# 02_-_MCU.net
KiCad netlist of a schematic drawn in Altium Designer
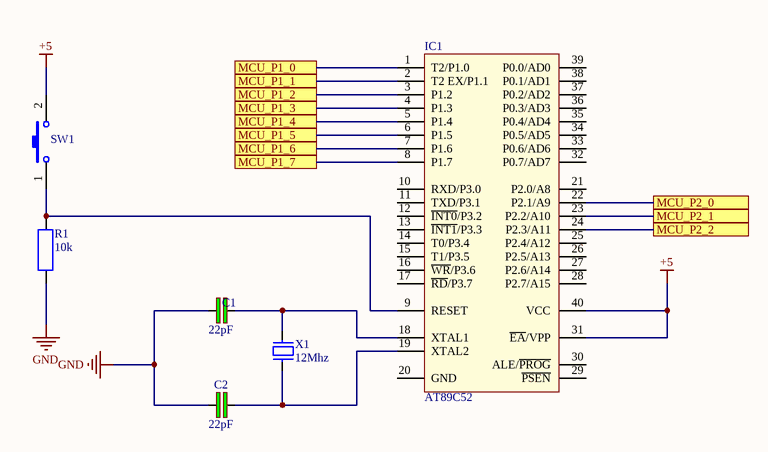
[diagram p0: [02] - MCU.SchDoc]

(export (version "E")
  (design (tool "Eeschema 10.0.6"))
  (components
    (comp (ref "C1")
      (value "22pF")
      (footprint "CAP_0805")
      (description "Cap SMD")
      (libsource (lib "My Library") (part "C"))
    )
    (comp (ref "C2")
      (value "22pF")
      (footprint "CAP_0805")
      (description "Cap SMD")
      (libsource (lib "My Library") (part "C"))
    )
    (comp (ref "IC1")
      (value "AT89C52")
      (footprint "DIP40/W0.6")
      (description "Atmel AT89C52, 8k Byte Flash Memory , 40 Pin")
      (libsource (lib "My Library") (part "AT89C52"))
    )
    (comp (ref "R1")
      (value "10k")
      (footprint "RES_SMD_0805")
      (description "Resistor 1W")
      (libsource (lib "My Library") (part "R1W"))
    )
    (comp (ref "SW1")
      (value "SW-2P-S")
      (footprint "SW-2P-S")
      (description "Switch Small 2 Pin")
      (fields (field (name "PUBLISHER") "Altium Limited"))
      (libsource (lib "My Library") (part "SW-2PIN-SMALL"))
    )
    (comp (ref "X1")
      (value "12Mhz")
      (footprint "XT2")
      (description "Crystal For all Crystal 2pin.")
      (libsource (lib "My Library") (part "XT2"))
    )
  )
  (nets
    (net (code "1") (name "+5") (class "Default")
      (node (ref "IC1") (pin "31") (pinfunction "~{EA}/VPP_31") (pintype "passive"))
      (node (ref "IC1") (pin "40") (pinfunction "VCC_40") (pintype "power_in"))
      (node (ref "SW1") (pin "2") (pinfunction "2_2") (pintype "passive"))
    )
    (net (code "2") (name "/MCU_P1_0") (class "Default")
      (node (ref "IC1") (pin "1") (pinfunction "T2/P1.0_1") (pintype "passive"))
    )
    (net (code "3") (name "/MCU_P1_1") (class "Default")
      (node (ref "IC1") (pin "2") (pinfunction "T2_EX/P1.1_2") (pintype "passive"))
    )
    (net (code "4") (name "/MCU_P1_2") (class "Default")
      (node (ref "IC1") (pin "3") (pinfunction "P1.2_3") (pintype "passive"))
    )
    (net (code "5") (name "/MCU_P1_3") (class "Default")
      (node (ref "IC1") (pin "4") (pinfunction "P1.3_4") (pintype "passive"))
    )
    (net (code "6") (name "/MCU_P1_4") (class "Default")
      (node (ref "IC1") (pin "5") (pinfunction "P1.4_5") (pintype "passive"))
    )
    (net (code "7") (name "/MCU_P1_5") (class "Default")
      (node (ref "IC1") (pin "6") (pinfunction "P1.5_6") (pintype "passive"))
    )
    (net (code "8") (name "/MCU_P1_6") (class "Default")
      (node (ref "IC1") (pin "7") (pinfunction "P1.6_7") (pintype "passive"))
    )
    (net (code "9") (name "/MCU_P1_7") (class "Default")
      (node (ref "IC1") (pin "8") (pinfunction "P1.7_8") (pintype "passive"))
    )
    (net (code "10") (name "/MCU_P2_0") (class "Default")
      (node (ref "IC1") (pin "22") (pinfunction "P2.1/A9_22") (pintype "passive"))
    )
    (net (code "11") (name "/MCU_P2_1") (class "Default")
      (node (ref "IC1") (pin "23") (pinfunction "P2.2/A10_23") (pintype "passive"))
    )
    (net (code "12") (name "/MCU_P2_2") (class "Default")
      (node (ref "IC1") (pin "24") (pinfunction "P2.3/A11_24") (pintype "passive"))
    )
    (net (code "13") (name "GND") (class "Default")
      (node (ref "C1") (pin "1") (pinfunction "1_1") (pintype "passive"))
      (node (ref "C2") (pin "1") (pinfunction "1_1") (pintype "passive"))
      (node (ref "R1") (pin "1") (pinfunction "1_1") (pintype "passive"))
    )
    (net (code "14") (name "Net-(IC1-RESET)") (class "Default")
      (node (ref "IC1") (pin "9") (pinfunction "RESET_9") (pintype "passive"))
      (node (ref "R1") (pin "2") (pinfunction "2_2") (pintype "passive"))
      (node (ref "SW1") (pin "1") (pinfunction "1_1") (pintype "passive"))
    )
    (net (code "15") (name "Net-(IC1-XTAL1)") (class "Default")
      (node (ref "C1") (pin "2") (pinfunction "2_2") (pintype "passive"))
      (node (ref "IC1") (pin "18") (pinfunction "XTAL1_18") (pintype "passive"))
      (node (ref "X1") (pin "2") (pinfunction "2_2") (pintype "passive"))
    )
    (net (code "16") (name "Net-(IC1-XTAL2)") (class "Default")
      (node (ref "C2") (pin "2") (pinfunction "2_2") (pintype "passive"))
      (node (ref "IC1") (pin "19") (pinfunction "XTAL2_19") (pintype "passive"))
      (node (ref "X1") (pin "1") (pinfunction "1_1") (pintype "passive"))
    )
    (net (code "17") (name "unconnected-(IC1-ALE{slash}~{PROG}-Pad30)") (class "Default")
      (node (ref "IC1") (pin "30") (pinfunction "ALE/~{PROG}_30") (pintype "passive"))
    )
    (net (code "18") (name "unconnected-(IC1-GND-Pad20)") (class "Default")
      (node (ref "IC1") (pin "20") (pinfunction "GND_20") (pintype "open_emitter"))
    )
    (net (code "19") (name "unconnected-(IC1-P0.0{slash}AD0-Pad39)") (class "Default")
      (node (ref "IC1") (pin "39") (pinfunction "P0.0/AD0_39") (pintype "passive"))
    )
    (net (code "20") (name "unconnected-(IC1-P0.1{slash}AD1-Pad38)") (class "Default")
      (node (ref "IC1") (pin "38") (pinfunction "P0.1/AD1_38") (pintype "passive"))
    )
    (net (code "21") (name "unconnected-(IC1-P0.2{slash}AD2-Pad37)") (class "Default")
      (node (ref "IC1") (pin "37") (pinfunction "P0.2/AD2_37") (pintype "passive"))
    )
    (net (code "22") (name "unconnected-(IC1-P0.3{slash}AD3-Pad36)") (class "Default")
      (node (ref "IC1") (pin "36") (pinfunction "P0.3/AD3_36") (pintype "passive"))
    )
    (net (code "23") (name "unconnected-(IC1-P0.4{slash}AD4-Pad35)") (class "Default")
      (node (ref "IC1") (pin "35") (pinfunction "P0.4/AD4_35") (pintype "passive"))
    )
    (net (code "24") (name "unconnected-(IC1-P0.5{slash}AD5-Pad34)") (class "Default")
      (node (ref "IC1") (pin "34") (pinfunction "P0.5/AD5_34") (pintype "passive"))
    )
    (net (code "25") (name "unconnected-(IC1-P0.6{slash}AD6-Pad33)") (class "Default")
      (node (ref "IC1") (pin "33") (pinfunction "P0.6/AD6_33") (pintype "passive"))
    )
    (net (code "26") (name "unconnected-(IC1-P0.7{slash}AD7-Pad32)") (class "Default")
      (node (ref "IC1") (pin "32") (pinfunction "P0.7/AD7_32") (pintype "passive"))
    )
    (net (code "27") (name "unconnected-(IC1-P2.0{slash}A8-Pad21)") (class "Default")
      (node (ref "IC1") (pin "21") (pinfunction "P2.0/A8_21") (pintype "passive"))
    )
    (net (code "28") (name "unconnected-(IC1-P2.4{slash}A12-Pad25)") (class "Default")
      (node (ref "IC1") (pin "25") (pinfunction "P2.4/A12_25") (pintype "passive"))
    )
    (net (code "29") (name "unconnected-(IC1-P2.5{slash}A13-Pad26)") (class "Default")
      (node (ref "IC1") (pin "26") (pinfunction "P2.5/A13_26") (pintype "passive"))
    )
    (net (code "30") (name "unconnected-(IC1-P2.6{slash}A14-Pad27)") (class "Default")
      (node (ref "IC1") (pin "27") (pinfunction "P2.6/A14_27") (pintype "passive"))
    )
    (net (code "31") (name "unconnected-(IC1-P2.7{slash}A15-Pad28)") (class "Default")
      (node (ref "IC1") (pin "28") (pinfunction "P2.7/A15_28") (pintype "passive"))
    )
    (net (code "32") (name "unconnected-(IC1-RXD{slash}P3.0-Pad10)") (class "Default")
      (node (ref "IC1") (pin "10") (pinfunction "RXD/P3.0_10") (pintype "passive"))
    )
    (net (code "33") (name "unconnected-(IC1-T0{slash}P3.4-Pad14)") (class "Default")
      (node (ref "IC1") (pin "14") (pinfunction "T0/P3.4_14") (pintype "passive"))
    )
    (net (code "34") (name "unconnected-(IC1-T1{slash}P3.5-Pad15)") (class "Default")
      (node (ref "IC1") (pin "15") (pinfunction "T1/P3.5_15") (pintype "passive"))
    )
    (net (code "35") (name "unconnected-(IC1-TXD{slash}P3.1-Pad11)") (class "Default")
      (node (ref "IC1") (pin "11") (pinfunction "TXD/P3.1_11") (pintype "passive"))
    )
    (net (code "36") (name "unconnected-(IC1-~{INT0}{slash}P3.2-Pad12)") (class "Default")
      (node (ref "IC1") (pin "12") (pinfunction "~{INT0}/P3.2_12") (pintype "passive"))
    )
    (net (code "37") (name "unconnected-(IC1-~{INT1}{slash}P3.3-Pad13)") (class "Default")
      (node (ref "IC1") (pin "13") (pinfunction "~{INT1}/P3.3_13") (pintype "passive"))
    )
    (net (code "38") (name "unconnected-(IC1-~{PSEN}-Pad29)") (class "Default")
      (node (ref "IC1") (pin "29") (pinfunction "~{PSEN}_29") (pintype "passive"))
    )
    (net (code "39") (name "unconnected-(IC1-~{RD}{slash}P3.7-Pad17)") (class "Default")
      (node (ref "IC1") (pin "17") (pinfunction "~{RD}/P3.7_17") (pintype "passive"))
    )
    (net (code "40") (name "unconnected-(IC1-~{WR}{slash}P3.6-Pad16)") (class "Default")
      (node (ref "IC1") (pin "16") (pinfunction "~{WR}/P3.6_16") (pintype "passive"))
    )
  )
)
